# SilentStepStick_v11.net
KiCad netlist of a schematic drawn in EAGLE
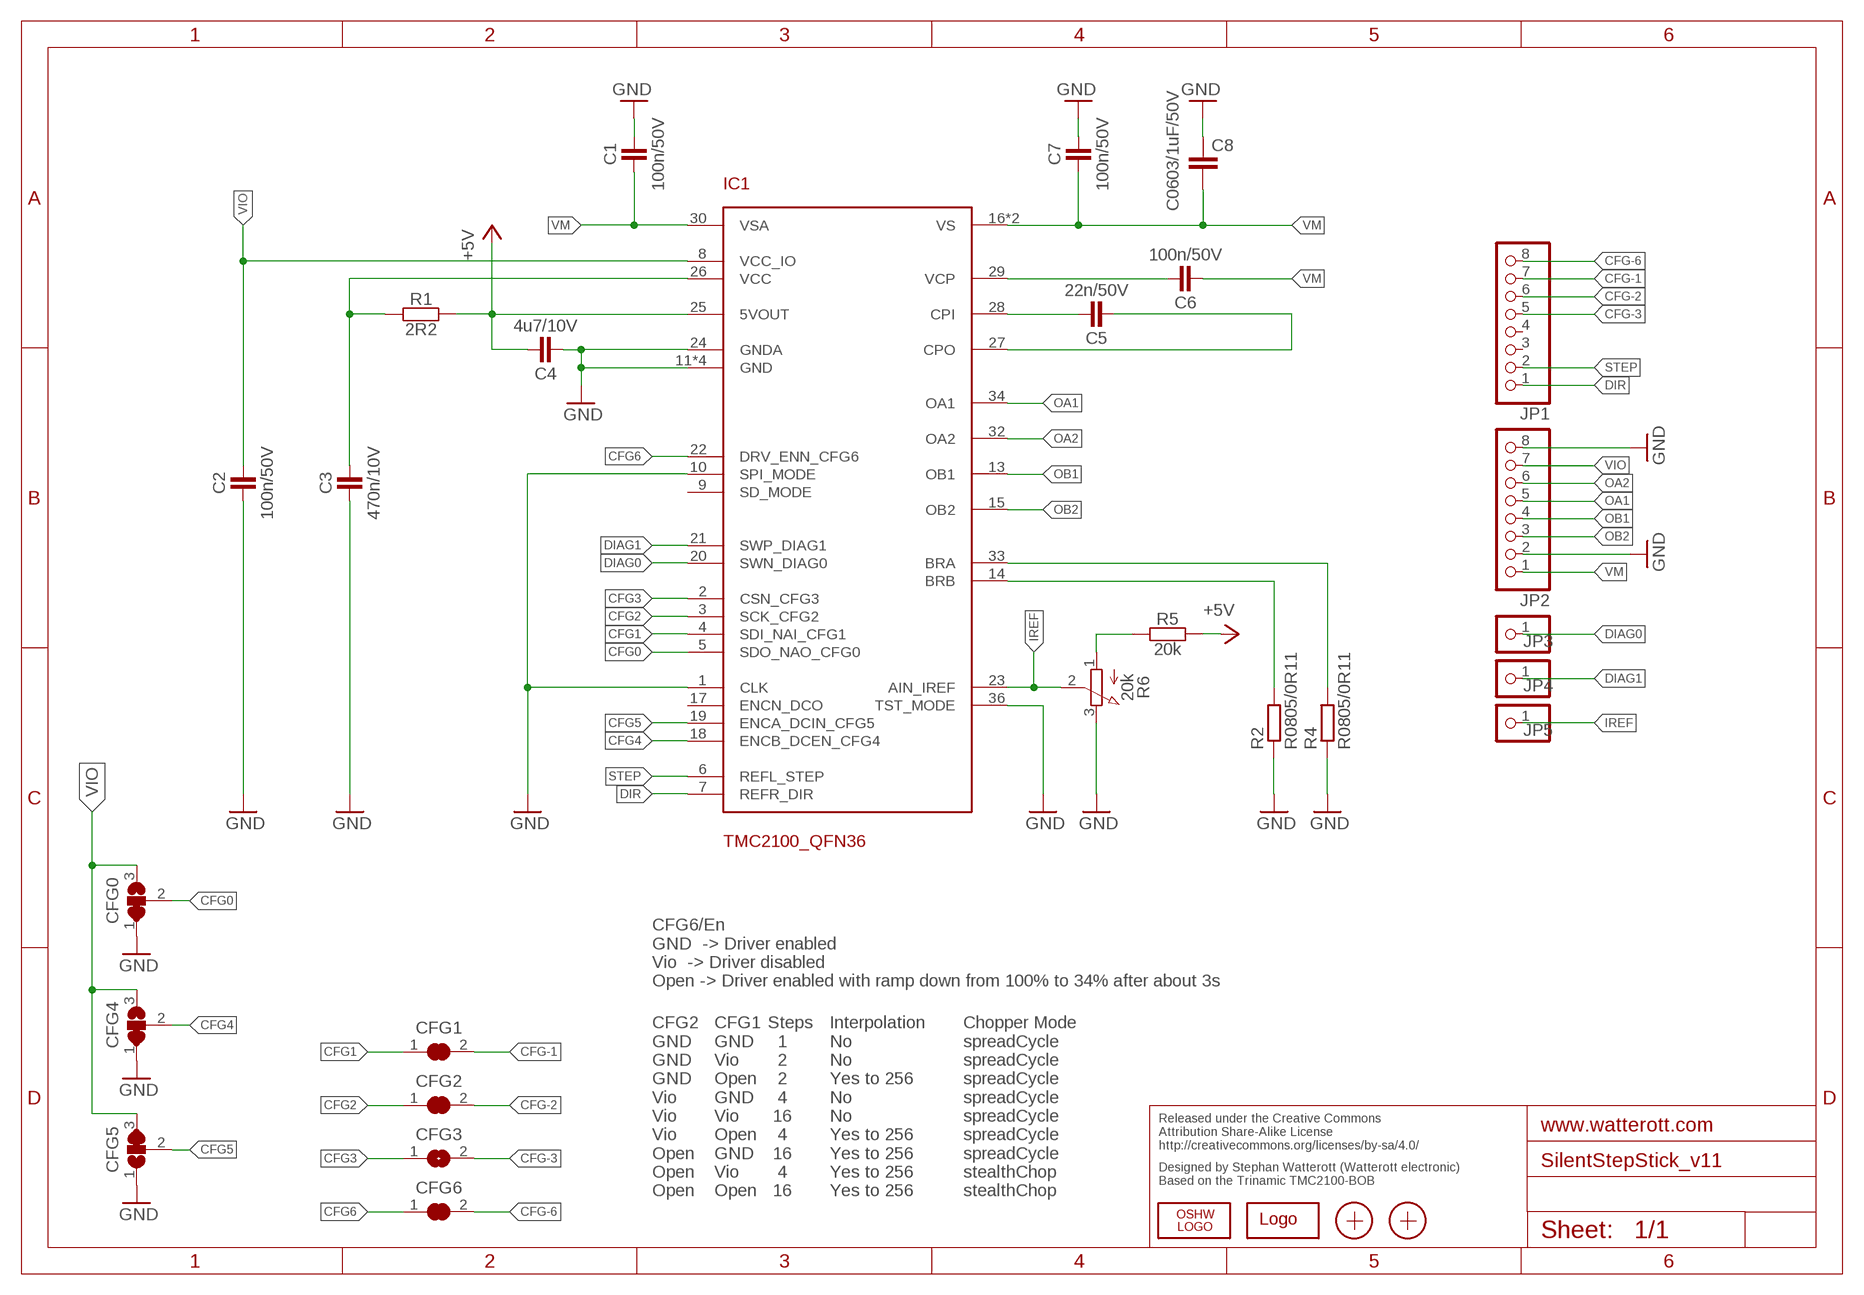
[diagram p0: schematic, sheet 1]

(export (version "E")
  (design (tool "Eeschema 10.0.6"))
  (components
    (comp (ref "C1")
      (value "100n/50V")
      (footprint "eagle-import:R0402")
      (libsource (lib "eagle-import") (part "CAPACITOR-C0402"))
    )
    (comp (ref "C2")
      (value "100n/50V")
      (footprint "eagle-import:R0402")
      (libsource (lib "eagle-import") (part "CAPACITOR-C0402"))
    )
    (comp (ref "C3")
      (value "470n/10V")
      (footprint "eagle-import:R0402")
      (libsource (lib "eagle-import") (part "CAPACITOR-C0402"))
    )
    (comp (ref "C4")
      (value "4u7/10V")
      (footprint "eagle-import:R0402")
      (libsource (lib "eagle-import") (part "CAPACITOR-C0402"))
    )
    (comp (ref "C5")
      (value "22n/50V")
      (footprint "eagle-import:R0402")
      (libsource (lib "eagle-import") (part "CAPACITOR-C0402"))
    )
    (comp (ref "C6")
      (value "100n/50V")
      (footprint "eagle-import:R0402")
      (libsource (lib "eagle-import") (part "CAPACITOR-C0402"))
    )
    (comp (ref "C7")
      (value "100n/50V")
      (footprint "eagle-import:R0402")
      (libsource (lib "eagle-import") (part "CAPACITOR-C0402"))
    )
    (comp (ref "C8")
      (value "C0603/1uF/50V")
      (footprint "eagle-import:C0603")
      (libsource (lib "eagle-import") (part "C-EUC0603"))
    )
    (comp (ref "CFG0")
      (value "JUMPER3-0201")
      (footprint "eagle-import:JUMPER3-0201")
      (libsource (lib "eagle-import") (part "JUMPER3-0201"))
    )
    (comp (ref "CFG1")
      (value "JUMPER2-0201")
      (footprint "eagle-import:JUMPER2-0201")
      (libsource (lib "eagle-import") (part "JUMPER2-0201"))
    )
    (comp (ref "CFG2")
      (value "JUMPER2-0201")
      (footprint "eagle-import:JUMPER2-0201")
      (libsource (lib "eagle-import") (part "JUMPER2-0201"))
    )
    (comp (ref "CFG3")
      (value "JUMPER2-0201")
      (footprint "eagle-import:JUMPER2-0201")
      (libsource (lib "eagle-import") (part "JUMPER2-0201"))
    )
    (comp (ref "CFG4")
      (value "JUMPER3-0201")
      (footprint "eagle-import:JUMPER3-0201")
      (libsource (lib "eagle-import") (part "JUMPER3-0201"))
    )
    (comp (ref "CFG5")
      (value "JUMPER3-0201")
      (footprint "eagle-import:JUMPER3-0201")
      (libsource (lib "eagle-import") (part "JUMPER3-0201"))
    )
    (comp (ref "CFG6")
      (value "JUMPER2-0201")
      (footprint "eagle-import:JUMPER2-0201")
      (libsource (lib "eagle-import") (part "JUMPER2-0201"))
    )
    (comp (ref "IC1")
      (value "TMC2100_QFN36")
      (footprint "eagle-import:QFN36")
      (libsource (lib "eagle-import") (part "TMC2100_QFN36"))
    )
    (comp (ref "JP1")
      (value "PINHD-1X08_2.54-S")
      (footprint "eagle-import:1X08-S")
      (libsource (lib "eagle-import") (part "PINHD-1X08_2.54-S"))
    )
    (comp (ref "JP2")
      (value "PINHD-1X08_2.54-S")
      (footprint "eagle-import:1X08-S")
      (libsource (lib "eagle-import") (part "PINHD-1X08_2.54-S"))
    )
    (comp (ref "JP3")
      (value "PINHD-1X1")
      (footprint "eagle-import:1X01")
      (libsource (lib "eagle-import") (part "PINHD-1X1"))
    )
    (comp (ref "JP4")
      (value "PINHD-1X1")
      (footprint "eagle-import:1X01")
      (libsource (lib "eagle-import") (part "PINHD-1X1"))
    )
    (comp (ref "JP5")
      (value "PINHD-1X1")
      (footprint "eagle-import:1X01")
      (libsource (lib "eagle-import") (part "PINHD-1X1"))
    )
    (comp (ref "LOGO1")
      (value "OSHW_LOGOX0070")
      (footprint "eagle-import:OSHW_6X70")
      (libsource (lib "eagle-import") (part "OSHW_LOGOX0070"))
    )
    (comp (ref "LOGO2")
      (value "LOGO-S_PLACE_M")
      (footprint "eagle-import:SPARK_TPLACE_M")
      (libsource (lib "eagle-import") (part "LOGO-S_PLACE_M"))
    )
    (comp (ref "R1")
      (value "2R2")
      (footprint "eagle-import:R0402")
      (libsource (lib "eagle-import") (part "RESISTOR-R0402"))
    )
    (comp (ref "R2")
      (value "R0805/0R11")
      (footprint "eagle-import:M0805")
      (libsource (lib "eagle-import") (part "R-EU_M0805"))
    )
    (comp (ref "R4")
      (value "R0805/0R11")
      (footprint "eagle-import:M0805")
      (libsource (lib "eagle-import") (part "R-EU_M0805"))
    )
    (comp (ref "R5")
      (value "20k")
      (footprint "eagle-import:R0402")
      (libsource (lib "eagle-import") (part "RESISTOR-R0402"))
    )
    (comp (ref "R6")
      (value "20k")
      (footprint "eagle-import:POT_EVM3R")
      (libsource (lib "eagle-import") (part "POTEVM3R"))
    )
    (comp (ref "X1")
      (value "PASSER-07")
      (footprint "eagle-import:PASSER_07MM")
      (libsource (lib "eagle-import") (part "PASSER-07"))
    )
    (comp (ref "X2")
      (value "PASSER-07")
      (footprint "eagle-import:PASSER_07MM")
      (libsource (lib "eagle-import") (part "PASSER-07"))
    )
  )
  (nets
    (net (code "1") (name "+5V") (class "Default")
      (node (ref "C4") (pin "2") (pinfunction "2_2") (pintype "passive"))
      (node (ref "IC1") (pin "25") (pinfunction "5VOUT_25") (pintype "bidirectional"))
      (node (ref "R1") (pin "2") (pinfunction "2_2") (pintype "passive"))
      (node (ref "R5") (pin "2") (pinfunction "2_2") (pintype "passive"))
    )
    (net (code "2") (name "CFG-1") (class "Default")
      (node (ref "CFG1") (pin "2") (pinfunction "2_2") (pintype "passive"))
      (node (ref "JP1") (pin "7") (pinfunction "7_7") (pintype "passive"))
    )
    (net (code "3") (name "CFG-2") (class "Default")
      (node (ref "CFG2") (pin "2") (pinfunction "2_2") (pintype "passive"))
      (node (ref "JP1") (pin "6") (pinfunction "6_6") (pintype "passive"))
    )
    (net (code "4") (name "CFG-3") (class "Default")
      (node (ref "CFG3") (pin "2") (pinfunction "2_2") (pintype "passive"))
      (node (ref "JP1") (pin "5") (pinfunction "5_5") (pintype "passive"))
    )
    (net (code "5") (name "CFG-6") (class "Default")
      (node (ref "CFG6") (pin "2") (pinfunction "2_2") (pintype "passive"))
      (node (ref "JP1") (pin "8") (pinfunction "8_8") (pintype "passive"))
    )
    (net (code "6") (name "CFG0") (class "Default")
      (node (ref "CFG0") (pin "2") (pinfunction "2_2") (pintype "passive"))
      (node (ref "IC1") (pin "5") (pinfunction "SDO_NAO_CFG0_5") (pintype "bidirectional"))
    )
    (net (code "7") (name "CFG1") (class "Default")
      (node (ref "CFG1") (pin "1") (pinfunction "1_1") (pintype "passive"))
      (node (ref "IC1") (pin "4") (pinfunction "SDI_NAI_CFG1_4") (pintype "bidirectional"))
    )
    (net (code "8") (name "CFG2") (class "Default")
      (node (ref "CFG2") (pin "1") (pinfunction "1_1") (pintype "passive"))
      (node (ref "IC1") (pin "3") (pinfunction "SCK_CFG2_3") (pintype "bidirectional"))
    )
    (net (code "9") (name "CFG3") (class "Default")
      (node (ref "CFG3") (pin "1") (pinfunction "1_1") (pintype "passive"))
      (node (ref "IC1") (pin "2") (pinfunction "CSN_CFG3_2") (pintype "bidirectional"))
    )
    (net (code "10") (name "CFG4") (class "Default")
      (node (ref "CFG4") (pin "2") (pinfunction "2_2") (pintype "passive"))
      (node (ref "IC1") (pin "18") (pinfunction "ENCB_DCEN_CFG4_18") (pintype "bidirectional"))
    )
    (net (code "11") (name "CFG5") (class "Default")
      (node (ref "CFG5") (pin "2") (pinfunction "2_2") (pintype "passive"))
      (node (ref "IC1") (pin "19") (pinfunction "ENCA_DCIN_CFG5_19") (pintype "bidirectional"))
    )
    (net (code "12") (name "CFG6") (class "Default")
      (node (ref "CFG6") (pin "1") (pinfunction "1_1") (pintype "passive"))
      (node (ref "IC1") (pin "22") (pinfunction "DRV_ENN_CFG6_22") (pintype "bidirectional"))
    )
    (net (code "13") (name "DIAG0") (class "Default")
      (node (ref "IC1") (pin "20") (pinfunction "SWN_DIAG0_20") (pintype "bidirectional"))
      (node (ref "JP3") (pin "1") (pinfunction "1_1") (pintype "passive"))
    )
    (net (code "14") (name "DIAG1") (class "Default")
      (node (ref "IC1") (pin "21") (pinfunction "SWP_DIAG1_21") (pintype "bidirectional"))
      (node (ref "JP4") (pin "1") (pinfunction "1_1") (pintype "passive"))
    )
    (net (code "15") (name "DIR") (class "Default")
      (node (ref "IC1") (pin "7") (pinfunction "REFR_DIR_7") (pintype "bidirectional"))
      (node (ref "JP1") (pin "1") (pinfunction "1_1") (pintype "passive"))
    )
    (net (code "16") (name "GND") (class "Default")
      (node (ref "C1") (pin "2") (pinfunction "2_2") (pintype "passive"))
      (node (ref "C2") (pin "1") (pinfunction "1_1") (pintype "passive"))
      (node (ref "C3") (pin "1") (pinfunction "1_1") (pintype "passive"))
      (node (ref "C4") (pin "1") (pinfunction "1_1") (pintype "passive"))
      (node (ref "C7") (pin "2") (pinfunction "2_2") (pintype "passive"))
      (node (ref "C8") (pin "2") (pinfunction "2_2") (pintype "passive"))
      (node (ref "CFG0") (pin "1") (pinfunction "1_1") (pintype "passive"))
      (node (ref "CFG4") (pin "1") (pinfunction "1_1") (pintype "passive"))
      (node (ref "CFG5") (pin "1") (pinfunction "1_1") (pintype "passive"))
      (node (ref "IC1") (pin "1") (pinfunction "CLK_1") (pintype "bidirectional"))
      (node (ref "IC1") (pin "10") (pinfunction "SPI_MODE_10") (pintype "bidirectional"))
      (node (ref "IC1") (pin "11") (pinfunction "GND_11") (pintype "bidirectional"))
      (node (ref "IC1") (pin "12") (pinfunction "GND_12") (pintype "bidirectional"))
      (node (ref "IC1") (pin "24") (pinfunction "GNDA_24") (pintype "bidirectional"))
      (node (ref "IC1") (pin "35") (pinfunction "GND_35") (pintype "bidirectional"))
      (node (ref "IC1") (pin "36") (pinfunction "TST_MODE_36") (pintype "bidirectional"))
      (node (ref "IC1") (pin "GND_PAD") (pinfunction "GND_GND_PAD") (pintype "bidirectional"))
      (node (ref "JP2") (pin "2") (pinfunction "2_2") (pintype "passive"))
      (node (ref "JP2") (pin "8") (pinfunction "8_8") (pintype "passive"))
      (node (ref "R2") (pin "1") (pinfunction "1_1") (pintype "passive"))
      (node (ref "R4") (pin "1") (pinfunction "1_1") (pintype "passive"))
      (node (ref "R6") (pin "3") (pinfunction "E_3") (pintype "passive"))
    )
    (net (code "17") (name "IREF") (class "Default")
      (node (ref "IC1") (pin "23") (pinfunction "AIN_IREF_23") (pintype "bidirectional"))
      (node (ref "JP5") (pin "1") (pinfunction "1_1") (pintype "passive"))
      (node (ref "R6") (pin "2") (pinfunction "S_2") (pintype "passive"))
    )
    (net (code "18") (name "Net-(IC1-BRA)") (class "Default")
      (node (ref "IC1") (pin "33") (pinfunction "BRA_33") (pintype "bidirectional"))
      (node (ref "R4") (pin "2") (pinfunction "2_2") (pintype "passive"))
    )
    (net (code "19") (name "Net-(IC1-BRB)") (class "Default")
      (node (ref "IC1") (pin "14") (pinfunction "BRB_14") (pintype "bidirectional"))
      (node (ref "R2") (pin "2") (pinfunction "2_2") (pintype "passive"))
    )
    (net (code "20") (name "Net-(IC1-CPI)") (class "Default")
      (node (ref "C5") (pin "2") (pinfunction "2_2") (pintype "passive"))
      (node (ref "IC1") (pin "28") (pinfunction "CPI_28") (pintype "bidirectional"))
    )
    (net (code "21") (name "Net-(IC1-CPO)") (class "Default")
      (node (ref "C5") (pin "1") (pinfunction "1_1") (pintype "passive"))
      (node (ref "IC1") (pin "27") (pinfunction "CPO_27") (pintype "bidirectional"))
    )
    (net (code "22") (name "Net-(IC1-VCC)") (class "Default")
      (node (ref "C3") (pin "2") (pinfunction "2_2") (pintype "passive"))
      (node (ref "IC1") (pin "26") (pinfunction "VCC_26") (pintype "bidirectional"))
      (node (ref "R1") (pin "1") (pinfunction "1_1") (pintype "passive"))
    )
    (net (code "23") (name "Net-(IC1-VCP)") (class "Default")
      (node (ref "C6") (pin "2") (pinfunction "2_2") (pintype "passive"))
      (node (ref "IC1") (pin "29") (pinfunction "VCP_29") (pintype "bidirectional"))
    )
    (net (code "24") (name "Net-(R6-A)") (class "Default")
      (node (ref "R5") (pin "1") (pinfunction "1_1") (pintype "passive"))
      (node (ref "R6") (pin "1") (pinfunction "A_1") (pintype "passive"))
    )
    (net (code "25") (name "OA1") (class "Default")
      (node (ref "IC1") (pin "34") (pinfunction "OA1_34") (pintype "bidirectional"))
      (node (ref "JP2") (pin "5") (pinfunction "5_5") (pintype "passive"))
    )
    (net (code "26") (name "OA2") (class "Default")
      (node (ref "IC1") (pin "32") (pinfunction "OA2_32") (pintype "bidirectional"))
      (node (ref "JP2") (pin "6") (pinfunction "6_6") (pintype "passive"))
    )
    (net (code "27") (name "OB1") (class "Default")
      (node (ref "IC1") (pin "13") (pinfunction "OB1_13") (pintype "bidirectional"))
      (node (ref "JP2") (pin "4") (pinfunction "4_4") (pintype "passive"))
    )
    (net (code "28") (name "OB2") (class "Default")
      (node (ref "IC1") (pin "15") (pinfunction "OB2_15") (pintype "bidirectional"))
      (node (ref "JP2") (pin "3") (pinfunction "3_3") (pintype "passive"))
    )
    (net (code "29") (name "STEP") (class "Default")
      (node (ref "IC1") (pin "6") (pinfunction "REFL_STEP_6") (pintype "bidirectional"))
      (node (ref "JP1") (pin "2") (pinfunction "2_2") (pintype "passive"))
    )
    (net (code "30") (name "VIO") (class "Default")
      (node (ref "C2") (pin "2") (pinfunction "2_2") (pintype "passive"))
      (node (ref "CFG0") (pin "3") (pinfunction "3_3") (pintype "passive"))
      (node (ref "CFG4") (pin "3") (pinfunction "3_3") (pintype "passive"))
      (node (ref "CFG5") (pin "3") (pinfunction "3_3") (pintype "passive"))
      (node (ref "IC1") (pin "8") (pinfunction "VCC_IO_8") (pintype "bidirectional"))
      (node (ref "JP2") (pin "7") (pinfunction "7_7") (pintype "passive"))
    )
    (net (code "31") (name "VM") (class "Default")
      (node (ref "C1") (pin "1") (pinfunction "1_1") (pintype "passive"))
      (node (ref "C6") (pin "1") (pinfunction "1_1") (pintype "passive"))
      (node (ref "C7") (pin "1") (pinfunction "1_1") (pintype "passive"))
      (node (ref "C8") (pin "1") (pinfunction "1_1") (pintype "passive"))
      (node (ref "IC1") (pin "16") (pinfunction "VS_16") (pintype "bidirectional"))
      (node (ref "IC1") (pin "30") (pinfunction "VSA_30") (pintype "bidirectional"))
      (node (ref "IC1") (pin "31") (pinfunction "VS_31") (pintype "bidirectional"))
      (node (ref "JP2") (pin "1") (pinfunction "1_1") (pintype "passive"))
    )
    (net (code "32") (name "unconnected-(IC1-ENCN_DCO-Pad17)") (class "Default")
      (node (ref "IC1") (pin "17") (pinfunction "ENCN_DCO_17") (pintype "bidirectional"))
    )
    (net (code "33") (name "unconnected-(IC1-SD_MODE-Pad9)") (class "Default")
      (node (ref "IC1") (pin "9") (pinfunction "SD_MODE_9") (pintype "bidirectional"))
    )
    (net (code "34") (name "unconnected-(JP1-Pad3)") (class "Default")
      (node (ref "JP1") (pin "3") (pinfunction "3_3") (pintype "passive"))
    )
    (net (code "35") (name "unconnected-(JP1-Pad4)") (class "Default")
      (node (ref "JP1") (pin "4") (pinfunction "4_4") (pintype "passive"))
    )
  )
)
